# shield_v9.net
KiCad netlist of a schematic drawn in EAGLE
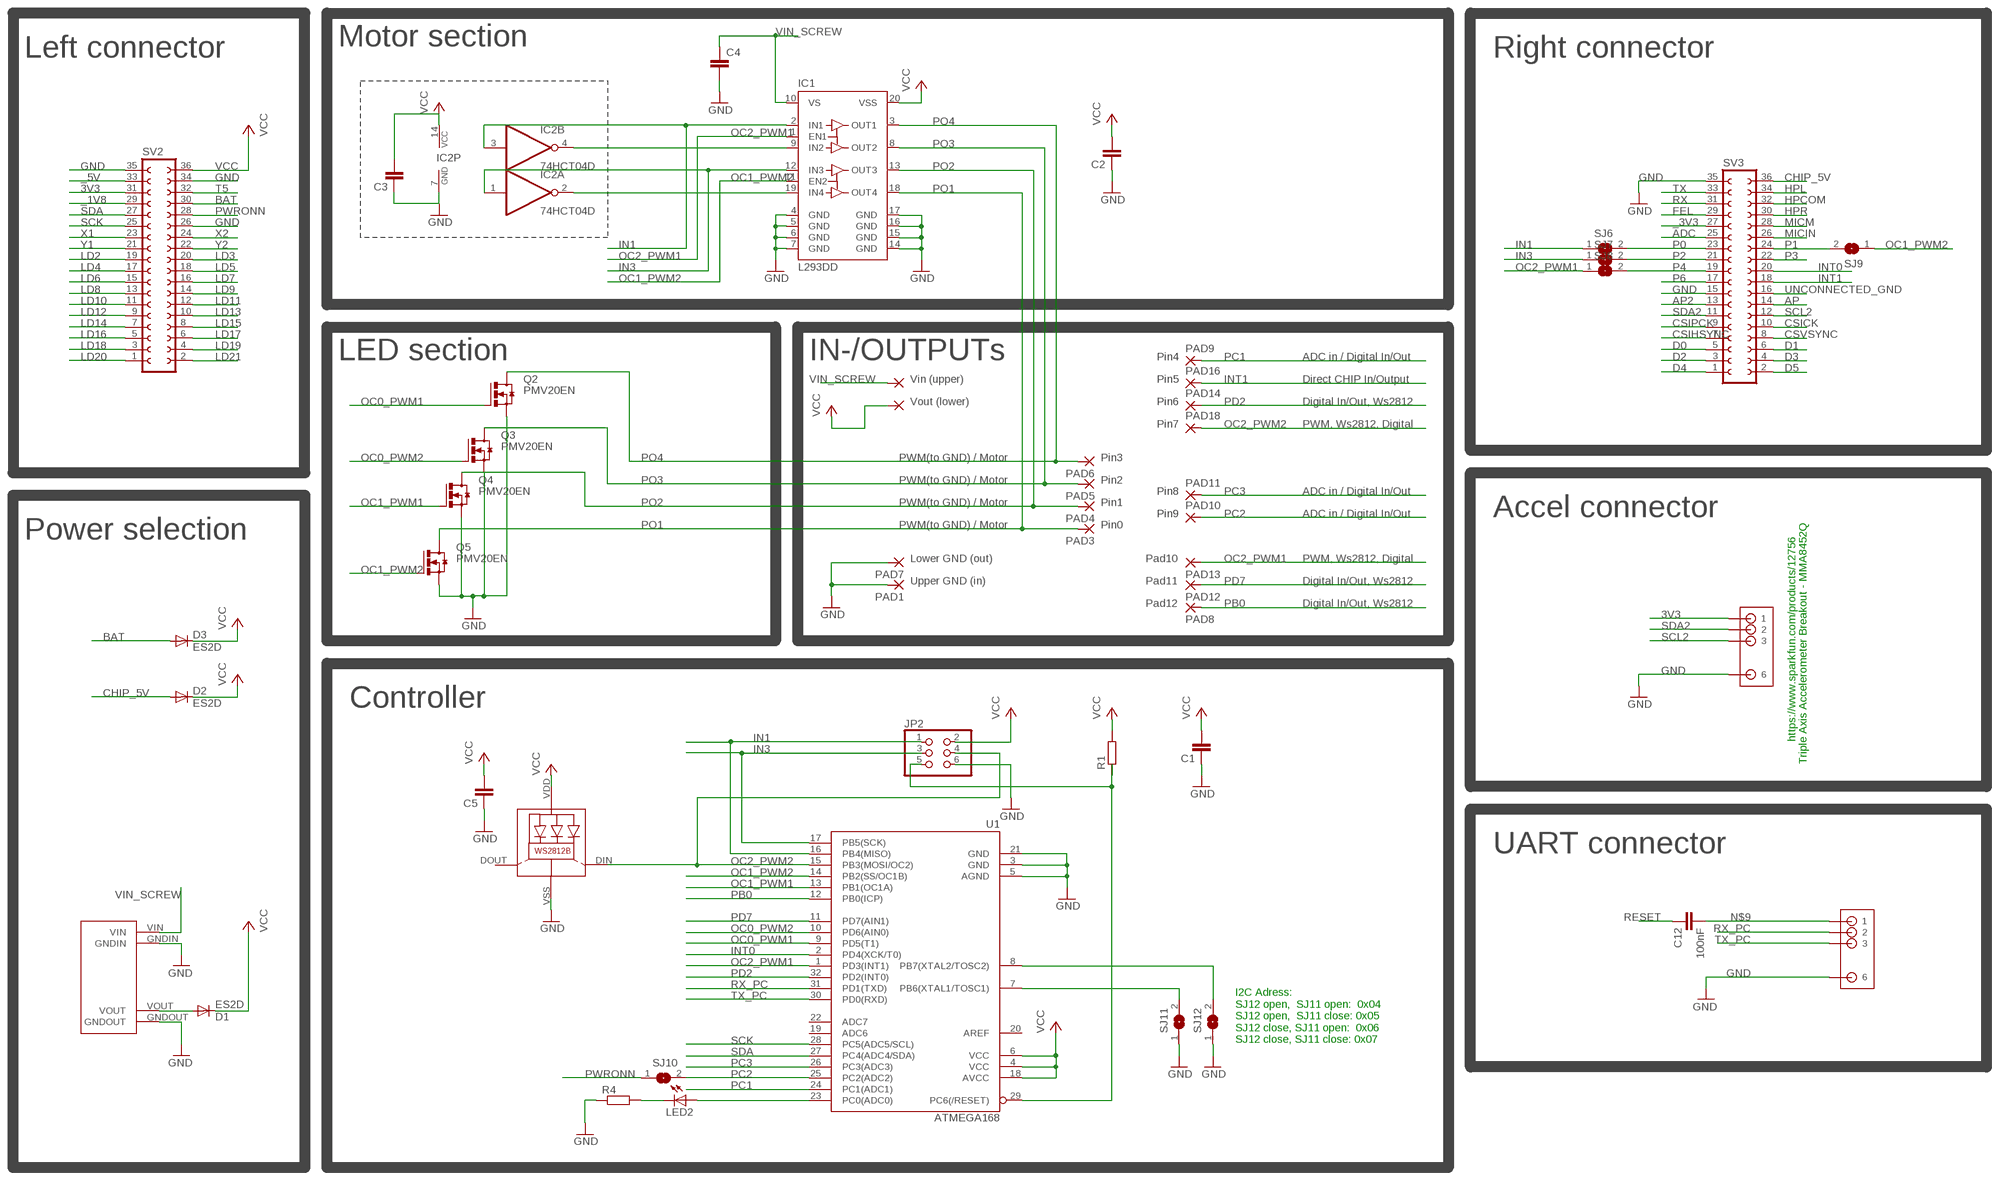
[diagram p0: schematic, sheet 1]

(export (version "E")
  (design (tool "Eeschema 10.0.6"))
  (components
    (comp (ref "C1")
      (value "C-EUC0805")
      (footprint "eagle-import:C0805")
      (libsource (lib "eagle-import") (part "C-EUC0805"))
    )
    (comp (ref "C2")
      (value "C-EUC0805")
      (footprint "eagle-import:C0805")
      (libsource (lib "eagle-import") (part "C-EUC0805"))
    )
    (comp (ref "C3")
      (value "C-EUC0805")
      (footprint "eagle-import:C0805")
      (libsource (lib "eagle-import") (part "C-EUC0805"))
    )
    (comp (ref "C4")
      (value "C-EUC1210")
      (footprint "eagle-import:C1210")
      (libsource (lib "eagle-import") (part "C-EUC1210"))
    )
    (comp (ref "C5")
      (value "C-EUC0805")
      (footprint "eagle-import:C0805")
      (libsource (lib "eagle-import") (part "C-EUC0805"))
    )
    (comp (ref "C12")
      (value "100nF")
      (footprint "eagle-import:C1206")
      (libsource (lib "eagle-import") (part "C-EUC1206"))
    )
    (comp (ref "D1")
      (value "ES2D")
      (footprint "eagle-import:SMB")
      (libsource (lib "eagle-import") (part "ES2D"))
    )
    (comp (ref "D2")
      (value "ES2D")
      (footprint "eagle-import:SMB")
      (libsource (lib "eagle-import") (part "ES2D"))
    )
    (comp (ref "D3")
      (value "ES2D")
      (footprint "eagle-import:SMB")
      (libsource (lib "eagle-import") (part "ES2D"))
    )
    (comp (ref "IC1")
      (value "L293DD")
      (footprint "eagle-import:SO20")
      (libsource (lib "eagle-import") (part "L293DD"))
    )
    (comp (ref "IC2")
      (value "74HCT04D")
      (footprint "eagle-import:SO14")
      (libsource (lib "eagle-import") (part "7404DHCT"))
    )
    (comp (ref "JP2")
      (value "PINHD-2X3")
      (footprint "eagle-import:2X03")
      (libsource (lib "eagle-import") (part "PINHD-2X3"))
    )
    (comp (ref "LED1")
      (value "WS2812B")
      (footprint "eagle-import:WS2812B")
      (libsource (lib "eagle-import") (part "WS2812B"))
    )
    (comp (ref "LED2")
      (value "LEDCHIP-LED0805")
      (footprint "eagle-import:CHIP-LED0805")
      (libsource (lib "eagle-import") (part "LEDCHIP-LED0805"))
    )
    (comp (ref "PAD1")
      (value "3,17/1,3")
      (footprint "eagle-import:3,17_1,3")
      (libsource (lib "eagle-import") (part "3,17/1,3"))
    )
    (comp (ref "PAD2")
      (value "3,17/1,3")
      (footprint "eagle-import:3,17_1,3")
      (libsource (lib "eagle-import") (part "3,17/1,3"))
    )
    (comp (ref "PAD3")
      (value "3,17/1,3")
      (footprint "eagle-import:3,17_1,3")
      (libsource (lib "eagle-import") (part "3,17/1,3"))
    )
    (comp (ref "PAD4")
      (value "3,17/1,3")
      (footprint "eagle-import:3,17_1,3")
      (libsource (lib "eagle-import") (part "3,17/1,3"))
    )
    (comp (ref "PAD5")
      (value "3,17/1,3")
      (footprint "eagle-import:3,17_1,3")
      (libsource (lib "eagle-import") (part "3,17/1,3"))
    )
    (comp (ref "PAD6")
      (value "3,17/1,3")
      (footprint "eagle-import:3,17_1,3")
      (libsource (lib "eagle-import") (part "3,17/1,3"))
    )
    (comp (ref "PAD7")
      (value "3,17/1,3")
      (footprint "eagle-import:3,17_1,3")
      (libsource (lib "eagle-import") (part "3,17/1,3"))
    )
    (comp (ref "PAD8")
      (value "WIREPADSMD1,27-254")
      (footprint "eagle-import:SMD1,27-2,54")
      (libsource (lib "eagle-import") (part "WIREPADSMD1,27-254"))
    )
    (comp (ref "PAD9")
      (value "3,17/1,3")
      (footprint "eagle-import:3,17_1,3")
      (libsource (lib "eagle-import") (part "3,17/1,3"))
    )
    (comp (ref "PAD10")
      (value "3,17/1,3")
      (footprint "eagle-import:3,17_1,3")
      (libsource (lib "eagle-import") (part "3,17/1,3"))
    )
    (comp (ref "PAD11")
      (value "3,17/1,3")
      (footprint "eagle-import:3,17_1,3")
      (libsource (lib "eagle-import") (part "3,17/1,3"))
    )
    (comp (ref "PAD12")
      (value "SMD2")
      (footprint "eagle-import:SMD1,27-2,54")
      (libsource (lib "eagle-import") (part "SMD2"))
    )
    (comp (ref "PAD13")
      (value "SMD2")
      (footprint "eagle-import:SMD1,27-2,54")
      (libsource (lib "eagle-import") (part "SMD2"))
    )
    (comp (ref "PAD14")
      (value "3,17/1,3")
      (footprint "eagle-import:3,17_1,3")
      (libsource (lib "eagle-import") (part "3,17/1,3"))
    )
    (comp (ref "PAD16")
      (value "3,17/1,3")
      (footprint "eagle-import:3,17_1,3")
      (libsource (lib "eagle-import") (part "3,17/1,3"))
    )
    (comp (ref "PAD17")
      (value "3,17/1,3")
      (footprint "eagle-import:3,17_1,3")
      (libsource (lib "eagle-import") (part "3,17/1,3"))
    )
    (comp (ref "PAD18")
      (value "3,17/1,3")
      (footprint "eagle-import:3,17_1,3")
      (libsource (lib "eagle-import") (part "3,17/1,3"))
    )
    (comp (ref "Q2")
      (value "PMV20EN")
      (footprint "eagle-import:SOT223")
      (libsource (lib "eagle-import") (part "NMOSFET_SMD_223"))
    )
    (comp (ref "Q3")
      (value "PMV20EN")
      (footprint "eagle-import:SOT223")
      (libsource (lib "eagle-import") (part "NMOSFET_SMD_223"))
    )
    (comp (ref "Q4")
      (value "PMV20EN")
      (footprint "eagle-import:SOT223")
      (libsource (lib "eagle-import") (part "NMOSFET_SMD_223"))
    )
    (comp (ref "Q5")
      (value "PMV20EN")
      (footprint "eagle-import:SOT223")
      (libsource (lib "eagle-import") (part "NMOSFET_SMD_223"))
    )
    (comp (ref "R1")
      (value "R-EU_M1206")
      (footprint "eagle-import:M1206")
      (libsource (lib "eagle-import") (part "R-EU_M1206"))
    )
    (comp (ref "R4")
      (value "R-EU_M1206")
      (footprint "eagle-import:M1206")
      (libsource (lib "eagle-import") (part "R-EU_M1206"))
    )
    (comp (ref "SJ6") (value "SJ") (footprint "eagle-import:SJ") (libsource (lib "eagle-import") (part "SJ")))
    (comp (ref "SJ7") (value "SJ") (footprint "eagle-import:SJ") (libsource (lib "eagle-import") (part "SJ")))
    (comp (ref "SJ8") (value "SJ") (footprint "eagle-import:SJ") (libsource (lib "eagle-import") (part "SJ")))
    (comp (ref "SJ9") (value "SJ") (footprint "eagle-import:SJ") (libsource (lib "eagle-import") (part "SJ")))
    (comp (ref "SJ10")
      (value "SJ")
      (footprint "eagle-import:SJ")
      (libsource (lib "eagle-import") (part "SJ"))
    )
    (comp (ref "SJ11")
      (value "SJ")
      (footprint "eagle-import:SJ")
      (libsource (lib "eagle-import") (part "SJ"))
    )
    (comp (ref "SJ12")
      (value "SJ")
      (footprint "eagle-import:SJ")
      (libsource (lib "eagle-import") (part "SJ"))
    )
    (comp (ref "SV2")
      (value "FE18-2")
      (footprint "eagle-import:FE18-2")
      (libsource (lib "eagle-import") (part "FE18-2"))
    )
    (comp (ref "SV3")
      (value "FE18-2")
      (footprint "eagle-import:FE18-2")
      (libsource (lib "eagle-import") (part "FE18-2"))
    )
    (comp (ref "U$1")
      (value "MP1584EN")
      (footprint "eagle-import:MP1584EN")
      (libsource (lib "eagle-import") (part "MP1584EN"))
    )
    (comp (ref "U$3")
      (value "6_TO_4_HEADER")
      (footprint "eagle-import:6_TO_4_HEADER")
      (libsource (lib "eagle-import") (part "6_TO_4_HEADER"))
    )
    (comp (ref "U$4")
      (value "6_TO_4_HEADER")
      (footprint "eagle-import:6_TO_4_HEADER")
      (libsource (lib "eagle-import") (part "6_TO_4_HEADER"))
    )
    (comp (ref "U1")
      (value "ATMEGA168")
      (footprint "eagle-import:TQFP32-08")
      (libsource (lib "eagle-import") (part "ATMEGA168"))
    )
  )
  (nets
    (net (code "1") (name "/3V3") (class "Default")
      (node (ref "SV2") (pin "31") (pinfunction "31_31") (pintype "passive"))
      (node (ref "U$4") (pin "1") (pinfunction "1_1") (pintype "bidirectional"))
    )
    (net (code "2") (name "/ADC") (class "Default")
      (node (ref "SV3") (pin "25") (pinfunction "25_25") (pintype "passive"))
    )
    (net (code "3") (name "/AP") (class "Default")
      (node (ref "SV3") (pin "14") (pinfunction "14_14") (pintype "passive"))
    )
    (net (code "4") (name "/AP2") (class "Default")
      (node (ref "SV3") (pin "13") (pinfunction "13_13") (pintype "passive"))
    )
    (net (code "5") (name "/BAT") (class "Default")
      (node (ref "D3") (pin "A") (pinfunction "A_A") (pintype "passive"))
      (node (ref "SV2") (pin "30") (pinfunction "30_30") (pintype "passive"))
    )
    (net (code "6") (name "/CHIP_5V") (class "Default")
      (node (ref "D2") (pin "A") (pinfunction "A_A") (pintype "passive"))
      (node (ref "SV3") (pin "36") (pinfunction "36_36") (pintype "passive"))
    )
    (net (code "7") (name "/CSICK") (class "Default")
      (node (ref "SV3") (pin "10") (pinfunction "10_10") (pintype "passive"))
    )
    (net (code "8") (name "/CSIHSYNC") (class "Default")
      (node (ref "SV3") (pin "7") (pinfunction "7_7") (pintype "passive"))
    )
    (net (code "9") (name "/CSIPCK") (class "Default")
      (node (ref "SV3") (pin "9") (pinfunction "9_9") (pintype "passive"))
    )
    (net (code "10") (name "/CSVSYNC") (class "Default")
      (node (ref "SV3") (pin "8") (pinfunction "8_8") (pintype "passive"))
    )
    (net (code "11") (name "/D0") (class "Default")
      (node (ref "SV3") (pin "5") (pinfunction "5_5") (pintype "passive"))
    )
    (net (code "12") (name "/D1") (class "Default")
      (node (ref "SV3") (pin "6") (pinfunction "6_6") (pintype "passive"))
    )
    (net (code "13") (name "/D2") (class "Default")
      (node (ref "SV3") (pin "3") (pinfunction "3_3") (pintype "passive"))
    )
    (net (code "14") (name "/D3") (class "Default")
      (node (ref "SV3") (pin "4") (pinfunction "4_4") (pintype "passive"))
    )
    (net (code "15") (name "/D4") (class "Default")
      (node (ref "SV3") (pin "1") (pinfunction "1_1") (pintype "passive"))
    )
    (net (code "16") (name "/D5") (class "Default")
      (node (ref "SV3") (pin "2") (pinfunction "2_2") (pintype "passive"))
    )
    (net (code "17") (name "/FEL") (class "Default")
      (node (ref "SV3") (pin "29") (pinfunction "29_29") (pintype "passive"))
    )
    (net (code "18") (name "/HPCOM") (class "Default")
      (node (ref "SV3") (pin "32") (pinfunction "32_32") (pintype "passive"))
    )
    (net (code "19") (name "/HPL") (class "Default")
      (node (ref "SV3") (pin "34") (pinfunction "34_34") (pintype "passive"))
    )
    (net (code "20") (name "/HPR") (class "Default")
      (node (ref "SV3") (pin "30") (pinfunction "30_30") (pintype "passive"))
    )
    (net (code "21") (name "/IN1") (class "Default")
      (node (ref "IC1") (pin "2") (pinfunction "IN1_2") (pintype "input"))
      (node (ref "IC2") (pin "3") (pinfunction "I_3") (pintype "input"))
      (node (ref "JP2") (pin "1") (pinfunction "1_1") (pintype "passive"))
      (node (ref "SJ6") (pin "1") (pinfunction "1_1") (pintype "passive"))
      (node (ref "U1") (pin "16") (pinfunction "PB4(MISO)_16") (pintype "bidirectional"))
    )
    (net (code "22") (name "/IN3") (class "Default")
      (node (ref "IC1") (pin "12") (pinfunction "IN3_12") (pintype "input"))
      (node (ref "IC2") (pin "1") (pinfunction "I_1") (pintype "input"))
      (node (ref "JP2") (pin "3") (pinfunction "3_3") (pintype "passive"))
      (node (ref "SJ7") (pin "1") (pinfunction "1_1") (pintype "passive"))
      (node (ref "U1") (pin "17") (pinfunction "PB5(SCK)_17") (pintype "bidirectional"))
    )
    (net (code "23") (name "/INT0") (class "Default")
      (node (ref "SV3") (pin "20") (pinfunction "20_20") (pintype "passive"))
      (node (ref "U1") (pin "2") (pinfunction "PD4(XCK/T0)_2") (pintype "bidirectional"))
    )
    (net (code "24") (name "/INT1") (class "Default")
      (node (ref "PAD16") (pin "1") (pinfunction "P_1") (pintype "passive"))
      (node (ref "SV3") (pin "18") (pinfunction "18_18") (pintype "passive"))
    )
    (net (code "25") (name "/LD2") (class "Default")
      (node (ref "SV2") (pin "19") (pinfunction "19_19") (pintype "passive"))
    )
    (net (code "26") (name "/LD3") (class "Default")
      (node (ref "SV2") (pin "20") (pinfunction "20_20") (pintype "passive"))
    )
    (net (code "27") (name "/LD4") (class "Default")
      (node (ref "SV2") (pin "17") (pinfunction "17_17") (pintype "passive"))
    )
    (net (code "28") (name "/LD5") (class "Default")
      (node (ref "SV2") (pin "18") (pinfunction "18_18") (pintype "passive"))
    )
    (net (code "29") (name "/LD6") (class "Default")
      (node (ref "SV2") (pin "15") (pinfunction "15_15") (pintype "passive"))
    )
    (net (code "30") (name "/LD7") (class "Default")
      (node (ref "SV2") (pin "16") (pinfunction "16_16") (pintype "passive"))
    )
    (net (code "31") (name "/LD8") (class "Default")
      (node (ref "SV2") (pin "13") (pinfunction "13_13") (pintype "passive"))
    )
    (net (code "32") (name "/LD9") (class "Default")
      (node (ref "SV2") (pin "14") (pinfunction "14_14") (pintype "passive"))
    )
    (net (code "33") (name "/LD10") (class "Default")
      (node (ref "SV2") (pin "11") (pinfunction "11_11") (pintype "passive"))
    )
    (net (code "34") (name "/LD11") (class "Default")
      (node (ref "SV2") (pin "12") (pinfunction "12_12") (pintype "passive"))
    )
    (net (code "35") (name "/LD12") (class "Default")
      (node (ref "SV2") (pin "9") (pinfunction "9_9") (pintype "passive"))
    )
    (net (code "36") (name "/LD13") (class "Default")
      (node (ref "SV2") (pin "10") (pinfunction "10_10") (pintype "passive"))
    )
    (net (code "37") (name "/LD14") (class "Default")
      (node (ref "SV2") (pin "7") (pinfunction "7_7") (pintype "passive"))
    )
    (net (code "38") (name "/LD15") (class "Default")
      (node (ref "SV2") (pin "8") (pinfunction "8_8") (pintype "passive"))
    )
    (net (code "39") (name "/LD16") (class "Default")
      (node (ref "SV2") (pin "5") (pinfunction "5_5") (pintype "passive"))
    )
    (net (code "40") (name "/LD17") (class "Default")
      (node (ref "SV2") (pin "6") (pinfunction "6_6") (pintype "passive"))
    )
    (net (code "41") (name "/LD18") (class "Default")
      (node (ref "SV2") (pin "3") (pinfunction "3_3") (pintype "passive"))
    )
    (net (code "42") (name "/LD19") (class "Default")
      (node (ref "SV2") (pin "4") (pinfunction "4_4") (pintype "passive"))
    )
    (net (code "43") (name "/LD20") (class "Default")
      (node (ref "SV2") (pin "1") (pinfunction "1_1") (pintype "passive"))
    )
    (net (code "44") (name "/LD21") (class "Default")
      (node (ref "SV2") (pin "2") (pinfunction "2_2") (pintype "passive"))
    )
    (net (code "45") (name "/MICIN") (class "Default")
      (node (ref "SV3") (pin "26") (pinfunction "26_26") (pintype "passive"))
    )
    (net (code "46") (name "/MICM") (class "Default")
      (node (ref "SV3") (pin "28") (pinfunction "28_28") (pintype "passive"))
    )
    (net (code "47") (name "/N$9") (class "Default")
      (node (ref "C12") (pin "2") (pinfunction "2_2") (pintype "passive"))
      (node (ref "U$3") (pin "1") (pinfunction "1_1") (pintype "bidirectional"))
    )
    (net (code "48") (name "/OC0_PWM1") (class "Default")
      (node (ref "Q2") (pin "1") (pinfunction "G_1") (pintype "passive"))
      (node (ref "U1") (pin "9") (pinfunction "PD5(T1)_9") (pintype "bidirectional"))
    )
    (net (code "49") (name "/OC0_PWM2") (class "Default")
      (node (ref "Q3") (pin "1") (pinfunction "G_1") (pintype "passive"))
      (node (ref "U1") (pin "10") (pinfunction "PD6(AIN0)_10") (pintype "bidirectional"))
    )
    (net (code "50") (name "/OC1_PWM1") (class "Default")
      (node (ref "Q4") (pin "1") (pinfunction "G_1") (pintype "passive"))
      (node (ref "U1") (pin "13") (pinfunction "PB1(OC1A)_13") (pintype "bidirectional"))
    )
    (net (code "51") (name "/OC1_PWM2") (class "Default")
      (node (ref "IC1") (pin "11") (pinfunction "EN2_11") (pintype "input"))
      (node (ref "Q5") (pin "1") (pinfunction "G_1") (pintype "passive"))
      (node (ref "SJ9") (pin "1") (pinfunction "1_1") (pintype "passive"))
      (node (ref "U1") (pin "14") (pinfunction "PB2(SS/OC1B)_14") (pintype "bidirectional"))
    )
    (net (code "52") (name "/OC2_PWM1") (class "Default")
      (node (ref "IC1") (pin "1") (pinfunction "EN1_1") (pintype "input"))
      (node (ref "PAD13") (pin "1") (pinfunction "P_1") (pintype "passive"))
      (node (ref "SJ8") (pin "1") (pinfunction "1_1") (pintype "passive"))
      (node (ref "U1") (pin "1") (pinfunction "PD3(INT1)_1") (pintype "bidirectional"))
    )
    (net (code "53") (name "/OC2_PWM2") (class "Default")
      (node (ref "JP2") (pin "4") (pinfunction "4_4") (pintype "passive"))
      (node (ref "LED1") (pin "DIN") (pinfunction "DI_DIN") (pintype "input"))
      (node (ref "PAD18") (pin "1") (pinfunction "P_1") (pintype "passive"))
      (node (ref "U1") (pin "15") (pinfunction "PB3(MOSI/OC2)_15") (pintype "bidirectional"))
    )
    (net (code "54") (name "/P0") (class "Default")
      (node (ref "SJ6") (pin "2") (pinfunction "2_2") (pintype "passive"))
      (node (ref "SV3") (pin "23") (pinfunction "23_23") (pintype "passive"))
    )
    (net (code "55") (name "/P1") (class "Default")
      (node (ref "SJ9") (pin "2") (pinfunction "2_2") (pintype "passive"))
      (node (ref "SV3") (pin "24") (pinfunction "24_24") (pintype "passive"))
    )
    (net (code "56") (name "/P2") (class "Default")
      (node (ref "SJ7") (pin "2") (pinfunction "2_2") (pintype "passive"))
      (node (ref "SV3") (pin "21") (pinfunction "21_21") (pintype "passive"))
    )
    (net (code "57") (name "/P3") (class "Default")
      (node (ref "SV3") (pin "22") (pinfunction "22_22") (pintype "passive"))
    )
    (net (code "58") (name "/P4") (class "Default")
      (node (ref "SJ8") (pin "2") (pinfunction "2_2") (pintype "passive"))
      (node (ref "SV3") (pin "19") (pinfunction "19_19") (pintype "passive"))
    )
    (net (code "59") (name "/P6") (class "Default")
      (node (ref "SV3") (pin "17") (pinfunction "17_17") (pintype "passive"))
    )
    (net (code "60") (name "/PB0") (class "Default")
      (node (ref "PAD8") (pin "1") (pinfunction "P_1") (pintype "passive"))
      (node (ref "U1") (pin "12") (pinfunction "PB0(ICP)_12") (pintype "bidirectional"))
    )
    (net (code "61") (name "/PC1") (class "Default")
      (node (ref "PAD9") (pin "1") (pinfunction "P_1") (pintype "passive"))
      (node (ref "U1") (pin "24") (pinfunction "PC1(ADC1)_24") (pintype "bidirectional"))
    )
    (net (code "62") (name "/PC2") (class "Default")
      (node (ref "PAD10") (pin "1") (pinfunction "P_1") (pintype "passive"))
      (node (ref "SJ10") (pin "2") (pinfunction "2_2") (pintype "passive"))
      (node (ref "U1") (pin "25") (pinfunction "PC2(ADC2)_25") (pintype "bidirectional"))
    )
    (net (code "63") (name "/PC3") (class "Default")
      (node (ref "PAD11") (pin "1") (pinfunction "P_1") (pintype "passive"))
      (node (ref "U1") (pin "26") (pinfunction "PC3(ADC3)_26") (pintype "bidirectional"))
    )
    (net (code "64") (name "/PD2") (class "Default")
      (node (ref "PAD14") (pin "1") (pinfunction "P_1") (pintype "passive"))
      (node (ref "U1") (pin "32") (pinfunction "PD2(INT0)_32") (pintype "bidirectional"))
    )
    (net (code "65") (name "/PD7") (class "Default")
      (node (ref "PAD12") (pin "1") (pinfunction "P_1") (pintype "passive"))
      (node (ref "U1") (pin "11") (pinfunction "PD7(AIN1)_11") (pintype "bidirectional"))
    )
    (net (code "66") (name "/PO1") (class "Default")
      (node (ref "IC1") (pin "18") (pinfunction "OUT4_18") (pintype "output"))
      (node (ref "PAD3") (pin "1") (pinfunction "P_1") (pintype "passive"))
      (node (ref "Q5") (pin "2") (pinfunction "D_2") (pintype "passive"))
      (node (ref "Q5") (pin "4") (pinfunction "D_4") (pintype "passive"))
    )
    (net (code "67") (name "/PO2") (class "Default")
      (node (ref "IC1") (pin "13") (pinfunction "OUT3_13") (pintype "output"))
      (node (ref "PAD4") (pin "1") (pinfunction "P_1") (pintype "passive"))
      (node (ref "Q4") (pin "2") (pinfunction "D_2") (pintype "passive"))
      (node (ref "Q4") (pin "4") (pinfunction "D_4") (pintype "passive"))
    )
    (net (code "68") (name "/PO3") (class "Default")
      (node (ref "IC1") (pin "8") (pinfunction "OUT2_8") (pintype "output"))
      (node (ref "PAD5") (pin "1") (pinfunction "P_1") (pintype "passive"))
      (node (ref "Q3") (pin "2") (pinfunction "D_2") (pintype "passive"))
      (node (ref "Q3") (pin "4") (pinfunction "D_4") (pintype "passive"))
    )
    (net (code "69") (name "/PO4") (class "Default")
      (node (ref "IC1") (pin "3") (pinfunction "OUT1_3") (pintype "output"))
      (node (ref "PAD6") (pin "1") (pinfunction "P_1") (pintype "passive"))
      (node (ref "Q2") (pin "2") (pinfunction "D_2") (pintype "passive"))
      (node (ref "Q2") (pin "4") (pinfunction "D_4") (pintype "passive"))
    )
    (net (code "70") (name "/PWRONN") (class "Default")
      (node (ref "SJ10") (pin "1") (pinfunction "1_1") (pintype "passive"))
      (node (ref "SV2") (pin "28") (pinfunction "28_28") (pintype "passive"))
    )
    (net (code "71") (name "/RESET") (class "Default")
      (node (ref "C12") (pin "1") (pinfunction "1_1") (pintype "passive"))
      (node (ref "JP2") (pin "5") (pinfunction "5_5") (pintype "passive"))
      (node (ref "R1") (pin "1") (pinfunction "1_1") (pintype "passive"))
      (node (ref "U1") (pin "29") (pinfunction "PC6(/RESET)_29") (pintype "bidirectional"))
    )
    (net (code "72") (name "/RX") (class "Default")
      (node (ref "SV3") (pin "31") (pinfunction "31_31") (pintype "passive"))
    )
    (net (code "73") (name "/RX_PC") (class "Default")
      (node (ref "U$3") (pin "2") (pinfunction "2_2") (pintype "bidirectional"))
      (node (ref "U1") (pin "31") (pinfunction "PD1(TXD)_31") (pintype "bidirectional"))
    )
    (net (code "74") (name "/SCK") (class "Default")
      (node (ref "SV2") (pin "25") (pinfunction "25_25") (pintype "passive"))
      (node (ref "U1") (pin "28") (pinfunction "PC5(ADC5/SCL)_28") (pintype "bidirectional"))
    )
    (net (code "75") (name "/SCL2") (class "Default")
      (node (ref "SV3") (pin "12") (pinfunction "12_12") (pintype "passive"))
      (node (ref "U$4") (pin "3") (pinfunction "3_3") (pintype "bidirectional"))
    )
    (net (code "76") (name "/SDA") (class "Default")
      (node (ref "SV2") (pin "27") (pinfunction "27_27") (pintype "passive"))
      (node (ref "U1") (pin "27") (pinfunction "PC4(ADC4/SDA)_27") (pintype "bidirectional"))
    )
    (net (code "77") (name "/SDA2") (class "Default")
      (node (ref "SV3") (pin "11") (pinfunction "11_11") (pintype "passive"))
      (node (ref "U$4") (pin "2") (pinfunction "2_2") (pintype "bidirectional"))
    )
    (net (code "78") (name "/T5") (class "Default")
      (node (ref "SV2") (pin "32") (pinfunction "32_32") (pintype "passive"))
    )
    (net (code "79") (name "/TX") (class "Default")
      (node (ref "SV3") (pin "33") (pinfunction "33_33") (pintype "passive"))
    )
    (net (code "80") (name "/TX_PC") (class "Default")
      (node (ref "U$3") (pin "3") (pinfunction "3_3") (pintype "bidirectional"))
      (node (ref "U1") (pin "30") (pinfunction "PD0(RXD)_30") (pintype "bidirectional"))
    )
    (net (code "81") (name "/UNCONNECTED_GND") (class "Default")
      (node (ref "SV3") (pin "16") (pinfunction "16_16") (pintype "passive"))
    )
    (net (code "82") (name "/VIN_SCREW") (class "Default")
      (node (ref "C4") (pin "1") (pinfunction "1_1") (pintype "passive"))
      (node (ref "IC1") (pin "10") (pinfunction "VS_10") (pintype "power_in"))
      (node (ref "PAD2") (pin "1") (pinfunction "P_1") (pintype "passive"))
      (node (ref "U$1") (pin "VIN") (pinfunction "VIN_VIN") (pintype "power_in"))
    )
    (net (code "83") (name "/X1") (class "Default")
      (node (ref "SV2") (pin "23") (pinfunction "23_23") (pintype "passive"))
    )
    (net (code "84") (name "/X2") (class "Default")
      (node (ref "SV2") (pin "24") (pinfunction "24_24") (pintype "passive"))
    )
    (net (code "85") (name "/Y1") (class "Default")
      (node (ref "SV2") (pin "21") (pinfunction "21_21") (pintype "passive"))
    )
    (net (code "86") (name "/Y2") (class "Default")
      (node (ref "SV2") (pin "22") (pinfunction "22_22") (pintype "passive"))
    )
    (net (code "87") (name "/_1V8") (class "Default")
      (node (ref "SV2") (pin "29") (pinfunction "29_29") (pintype "passive"))
    )
    (net (code "88") (name "/_3V3") (class "Default")
      (node (ref "SV3") (pin "27") (pinfunction "27_27") (pintype "passive"))
    )
    (net (code "89") (name "/_5V") (class "Default")
      (node (ref "SV2") (pin "33") (pinfunction "33_33") (pintype "passive"))
    )
    (net (code "90") (name "GND") (class "Default")
      (node (ref "C1") (pin "1") (pinfunction "1_1") (pintype "passive"))
      (node (ref "C2") (pin "1") (pinfunction "1_1") (pintype "passive"))
      (node (ref "C3") (pin "1") (pinfunction "1_1") (pintype "passive"))
      (node (ref "C4") (pin "2") (pinfunction "2_2") (pintype "passive"))
      (node (ref "C5") (pin "1") (pinfunction "1_1") (pintype "passive"))
      (node (ref "IC1") (pin "14") (pinfunction "GND_14") (pintype "power_in"))
      (node (ref "IC1") (pin "15") (pinfunction "GND_15") (pintype "power_in"))
      (node (ref "IC1") (pin "16") (pinfunction "GND_16") (pintype "power_in"))
      (node (ref "IC1") (pin "17") (pinfunction "GND_17") (pintype "power_in"))
      (node (ref "IC1") (pin "4") (pinfunction "GND_4") (pintype "power_in"))
      (node (ref "IC1") (pin "5") (pinfunction "GND_5") (pintype "power_in"))
      (node (ref "IC1") (pin "6") (pinfunction "GND_6") (pintype "power_in"))
      (node (ref "IC1") (pin "7") (pinfunction "GND_7") (pintype "power_in"))
      (node (ref "IC2") (pin "7") (pinfunction "GND_7") (pintype "power_in"))
      (node (ref "JP2") (pin "6") (pinfunction "6_6") (pintype "passive"))
      (node (ref "LED1") (pin "VSS") (pinfunction "GND_VSS") (pintype "power_in"))
      (node (ref "PAD1") (pin "1") (pinfunction "P_1") (pintype "passive"))
      (node (ref "PAD7") (pin "1") (pinfunction "P_1") (pintype "passive"))
      (node (ref "Q2") (pin "3") (pinfunction "S_3") (pintype "passive"))
      (node (ref "Q3") (pin "3") (pinfunction "S_3") (pintype "passive"))
      (node (ref "Q4") (pin "3") (pinfunction "S_3") (pintype "passive"))
      (node (ref "Q5") (pin "3") (pinfunction "S_3") (pintype "passive"))
      (node (ref "R4") (pin "1") (pinfunction "1_1") (pintype "passive"))
      (node (ref "SJ11") (pin "1") (pinfunction "1_1") (pintype "passive"))
      (node (ref "SJ12") (pin "1") (pinfunction "1_1") (pintype "passive"))
      (node (ref "SV2") (pin "26") (pinfunction "26_26") (pintype "passive"))
      (node (ref "SV2") (pin "34") (pinfunction "34_34") (pintype "passive"))
      (node (ref "SV2") (pin "35") (pinfunction "35_35") (pintype "passive"))
      (node (ref "SV3") (pin "15") (pinfunction "15_15") (pintype "passive"))
      (node (ref "SV3") (pin "35") (pinfunction "35_35") (pintype "passive"))
      (node (ref "U$1") (pin "GNDIN") (pinfunction "GNDIN_GNDIN") (pintype "power_in"))
      (node (ref "U$1") (pin "GNDOUT") (pinfunction "GNDOUT_GNDOUT") (pintype "power_in"))
      (node (ref "U$3") (pin "6") (pinfunction "6_6") (pintype "bidirectional"))
      (node (ref "U$4") (pin "6") (pinfunction "6_6") (pintype "bidirectional"))
      (node (ref "U1") (pin "21") (pinfunction "GND_21") (pintype "bidirectional"))
      (node (ref "U1") (pin "3") (pinfunction "GND_3") (pintype "bidirectional"))
      (node (ref "U1") (pin "5") (pinfunction "AGND_5") (pintype "bidirectional"))
    )
    (net (code "91") (name "Net-(D1-PadA)") (class "Default")
      (node (ref "D1") (pin "A") (pinfunction "A_A") (pintype "passive"))
      (node (ref "U$1") (pin "VOUT") (pinfunction "VOUT_VOUT") (pintype "power_in"))
    )
    (net (code "92") (name "Net-(IC1-IN2)") (class "Default")
      (node (ref "IC1") (pin "9") (pinfunction "IN2_9") (pintype "input"))
      (node (ref "IC2") (pin "4") (pinfunction "O_4") (pintype "output"))
    )
    (net (code "93") (name "Net-(IC1-IN4)") (class "Default")
      (node (ref "IC1") (pin "19") (pinfunction "IN4_19") (pintype "input"))
      (node (ref "IC2") (pin "2") (pinfunction "O_2") (pintype "output"))
    )
    (net (code "94") (name "Net-(LED2-PadC)") (class "Default")
      (node (ref "LED2") (pin "C") (pinfunction "C_C") (pintype "passive"))
      (node (ref "R4") (pin "2") (pinfunction "2_2") (pintype "passive"))
    )
    (net (code "95") (name "Net-(U1-PB6(XTAL1{slash}TOSC1))") (class "Default")
      (node (ref "SJ11") (pin "2") (pinfunction "2_2") (pintype "passive"))
      (node (ref "U1") (pin "7") (pinfunction "PB6(XTAL1/TOSC1)_7") (pintype "bidirectional"))
    )
    (net (code "96") (name "Net-(U1-PB7(XTAL2{slash}TOSC2))") (class "Default")
      (node (ref "SJ12") (pin "2") (pinfunction "2_2") (pintype "passive"))
      (node (ref "U1") (pin "8") (pinfunction "PB7(XTAL2/TOSC2)_8") (pintype "bidirectional"))
    )
    (net (code "97") (name "Net-(U1-PC0(ADC0))") (class "Default")
      (node (ref "LED2") (pin "A") (pinfunction "A_A") (pintype "passive"))
      (node (ref "U1") (pin "23") (pinfunction "PC0(ADC0)_23") (pintype "bidirectional"))
    )
    (net (code "98") (name "VCC") (class "Default")
      (node (ref "C1") (pin "2") (pinfunction "2_2") (pintype "passive"))
      (node (ref "C2") (pin "2") (pinfunction "2_2") (pintype "passive"))
      (node (ref "C3") (pin "2") (pinfunction "2_2") (pintype "passive"))
      (node (ref "C5") (pin "2") (pinfunction "2_2") (pintype "passive"))
      (node (ref "D1") (pin "C") (pinfunction "C_C") (pintype "passive"))
      (node (ref "D2") (pin "C") (pinfunction "C_C") (pintype "passive"))
      (node (ref "D3") (pin "C") (pinfunction "C_C") (pintype "passive"))
      (node (ref "IC1") (pin "20") (pinfunction "VSS_20") (pintype "power_in"))
      (node (ref "IC2") (pin "14") (pinfunction "VCC_14") (pintype "power_in"))
      (node (ref "JP2") (pin "2") (pinfunction "2_2") (pintype "passive"))
      (node (ref "LED1") (pin "VDD") (pinfunction "VDD_VDD") (pintype "power_in"))
      (node (ref "PAD17") (pin "1") (pinfunction "P_1") (pintype "passive"))
      (node (ref "R1") (pin "2") (pinfunction "2_2") (pintype "passive"))
      (node (ref "SV2") (pin "36") (pinfunction "36_36") (pintype "passive"))
      (node (ref "U1") (pin "18") (pinfunction "AVCC_18") (pintype "bidirectional"))
      (node (ref "U1") (pin "4") (pinfunction "VCC_4") (pintype "bidirectional"))
      (node (ref "U1") (pin "6") (pinfunction "VCC_6") (pintype "bidirectional"))
    )
    (net (code "99") (name "unconnected-(LED1-DO-PadDOUT)") (class "Default")
      (node (ref "LED1") (pin "DOUT") (pinfunction "DO_DOUT") (pintype "output"))
    )
    (net (code "100") (name "unconnected-(U1-ADC6-Pad19)") (class "Default")
      (node (ref "U1") (pin "19") (pinfunction "ADC6_19") (pintype "bidirectional"))
    )
    (net (code "101") (name "unconnected-(U1-ADC7-Pad22)") (class "Default")
      (node (ref "U1") (pin "22") (pinfunction "ADC7_22") (pintype "bidirectional"))
    )
    (net (code "102") (name "unconnected-(U1-AREF-Pad20)") (class "Default")
      (node (ref "U1") (pin "20") (pinfunction "AREF_20") (pintype "bidirectional"))
    )
  )
)
